# USB_TO_UART.net
KiCad netlist of a schematic drawn in Altium Designer
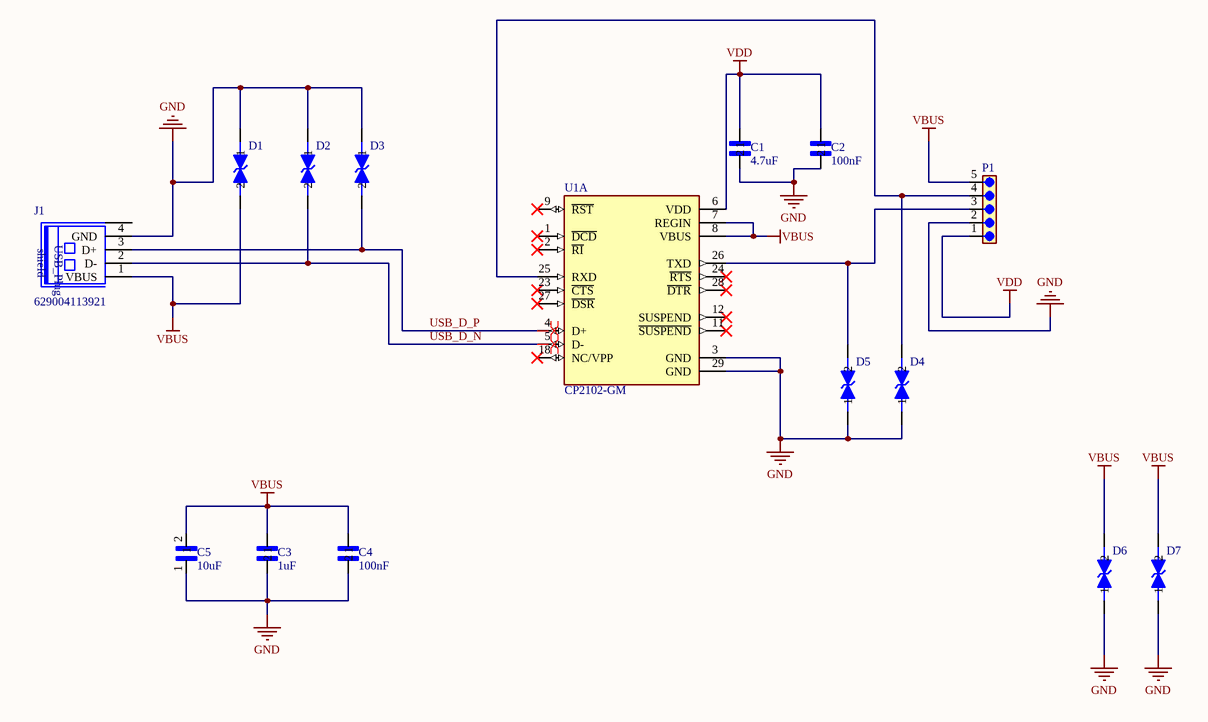
[diagram p0: USB_TO_UART_.SchDoc]

(export (version "E")
  (design (tool "Eeschema 10.0.6"))
  (components
    (comp (ref "C1")
      (value "4.7uF")
      (footprint "CAPC1005X65N")
      (fields (field (name "MF") "TDK") (field (name "MP") "C1005X5R1A475K050BC."))
      (libsource (lib "C1") (part "C1005X5R1A475K050BC"))
    )
    (comp (ref "C2")
      (value "100nF")
      (footprint "CAPC1005X55N")
      (description "0.1 ÂµF Â±10% 16V Ceramic Capacitor X7R 0402 (1005 Metric)")
      (fields (field (name "MF") "Yageo") (field (name "MP") "CC0402KRX7R7BB104"))
      (libsource (lib "C2") (part "CC0402KRX7R7BB104"))
    )
    (comp (ref "C3")
      (value "1uF")
      (footprint "CAPC1005X55N")
      (description "1 ÂµF Â±10% 10V Ceramic Capacitor X5R 0402 (1005 Metric)")
      (fields (field (name "MF") "KEMET") (field (name "MP") "C0402C105K8PACTU"))
      (libsource (lib "C3") (part "C0402C105K8PACTU"))
    )
    (comp (ref "C4")
      (value "100nF")
      (footprint "CAPC1005X55N")
      (description "0.1 ÂµF Â±10% 16V Ceramic Capacitor X7R 0402 (1005 Metric)")
      (fields (field (name "MF") "Yageo") (field (name "MP") "CC0402KRX7R7BB104"))
      (libsource (lib "C4") (part "CC0402KRX7R7BB104"))
    )
    (comp (ref "C5")
      (value "10uF")
      (footprint "CAPC1608X90N")
      (description "10ÂµF Â±10% 10V Ceramic Capacitor X5R 0603 (1608 Metric)")
      (fields (field (name "MP") "C1608X5R1A106K080AC") (field (name "MF") "TDK"))
      (libsource (lib "C5") (part "C1608X5R1A106K080AC"))
    )
    (comp (ref "D1")
      (value "~")
      (footprint "DIO_TPD1E10B06DPYR")
      (description "12-pF, Â±5.5V, Â±30-kV ESD protection diode in 0402 and SOD-523 package")
      (fields (field (name "MF") "Texas Instruments") (field (name "MP") "TPD1E10B06DPYR"))
      (libsource (lib "TPD1E10B06DPYR") (part "TPD1E10B06DPYR"))
    )
    (comp (ref "D2")
      (value "~")
      (footprint "DIO_TPD1E10B06DPYR")
      (description "12-pF, Â±5.5V, Â±30-kV ESD protection diode in 0402 and SOD-523 package")
      (fields (field (name "MF") "Texas Instruments") (field (name "MP") "TPD1E10B06DPYR"))
      (libsource (lib "TPD1E10B06DPYR") (part "TPD1E10B06DPYR"))
    )
    (comp (ref "D3")
      (value "~")
      (footprint "DIO_TPD1E10B06DPYR")
      (description "12-pF, Â±5.5V, Â±30-kV ESD protection diode in 0402 and SOD-523 package")
      (fields (field (name "MF") "Texas Instruments") (field (name "MP") "TPD1E10B06DPYR"))
      (libsource (lib "TPD1E10B06DPYR") (part "TPD1E10B06DPYR"))
    )
    (comp (ref "D4")
      (value "~")
      (footprint "DIO_TPD1E10B06DPYR")
      (description "12-pF, Â±5.5V, Â±30-kV ESD protection diode in 0402 and SOD-523 package")
      (fields (field (name "MF") "Texas Instruments") (field (name "MP") "TPD1E10B06DPYR"))
      (libsource (lib "TPD1E10B06DPYR") (part "TPD1E10B06DPYR"))
    )
    (comp (ref "D5")
      (value "~")
      (footprint "DIO_TPD1E10B06DPYR")
      (description "12-pF, Â±5.5V, Â±30-kV ESD protection diode in 0402 and SOD-523 package")
      (fields (field (name "MF") "Texas Instruments") (field (name "MP") "TPD1E10B06DPYR"))
      (libsource (lib "TPD1E10B06DPYR") (part "TPD1E10B06DPYR"))
    )
    (comp (ref "D6")
      (value "~")
      (footprint "DIO_TPD1E10B06DPYR")
      (description "12-pF, Â±5.5V, Â±30-kV ESD protection diode in 0402 and SOD-523 package")
      (fields (field (name "MF") "Texas Instruments") (field (name "MP") "TPD1E10B06DPYR"))
      (libsource (lib "TPD1E10B06DPYR") (part "TPD1E10B06DPYR"))
    )
    (comp (ref "D7")
      (value "~")
      (footprint "DIO_TPD1E10B06DPYR")
      (description "12-pF, Â±5.5V, Â±30-kV ESD protection diode in 0402 and SOD-523 package")
      (fields (field (name "MF") "Texas Instruments") (field (name "MP") "TPD1E10B06DPYR"))
      (libsource (lib "TPD1E10B06DPYR") (part "TPD1E10B06DPYR"))
    )
    (comp (ref "J1")
      (value "629004113921")
      (footprint "629004113921")
      (description "Type A Plug Horizontal SMT - with Clips")
      (fields (field (name "MF") "Wurth Electronics"))
      (libsource (lib "USB_J1") (part "629004113921"))
    )
    (comp (ref "P1")
      (value "~")
      (footprint "61300511021")
      (description "5 pins, 1 row, right angled, gold plating")
      (fields (field (name "MF") "Wurth Electronics") (field (name "MP") "61300511021"))
      (libsource (lib "6130XX11021_61300511021") (part "6130XX11021_61300511021"))
    )
    (comp (ref "U1A")
      (value "CP2102-GM")
      (footprint "QFN50P500X500X100-29N")
      (description "USB Bridge, USB to UART USB 2.0 UART Interface 28-QFN (5x5)")
      (fields (field (name "MF") "Silicon Labs"))
      (libsource (lib "CP2102-GM") (part "CP2102-GM"))
    )
  )
  (nets
    (net (code "1") (name "/USB_D_N") (class "Default")
      (node (ref "D2") (pin "2") (pinfunction "2_2") (pintype "passive"))
      (node (ref "J1") (pin "2") (pinfunction "D-_2") (pintype "passive"))
      (node (ref "U1A") (pin "5") (pinfunction "D-_5") (pintype "bidirectional"))
    )
    (net (code "2") (name "/USB_D_P") (class "Default")
      (node (ref "D3") (pin "2") (pinfunction "2_2") (pintype "passive"))
      (node (ref "J1") (pin "3") (pinfunction "D+_3") (pintype "passive"))
      (node (ref "U1A") (pin "4") (pinfunction "D+_4") (pintype "bidirectional"))
    )
    (net (code "3") (name "GND") (class "Default")
      (node (ref "C1") (pin "1") (pinfunction "1_1") (pintype "passive"))
      (node (ref "C2") (pin "1") (pinfunction "1_1") (pintype "passive"))
      (node (ref "C3") (pin "1") (pinfunction "1_1") (pintype "passive"))
      (node (ref "C4") (pin "1") (pinfunction "1_1") (pintype "passive"))
      (node (ref "C5") (pin "1") (pinfunction "1_1") (pintype "passive"))
      (node (ref "D1") (pin "1") (pinfunction "1_1") (pintype "passive"))
      (node (ref "D2") (pin "1") (pinfunction "1_1") (pintype "passive"))
      (node (ref "D3") (pin "1") (pinfunction "1_1") (pintype "passive"))
      (node (ref "D4") (pin "1") (pinfunction "1_1") (pintype "passive"))
      (node (ref "D5") (pin "1") (pinfunction "1_1") (pintype "passive"))
      (node (ref "D6") (pin "1") (pinfunction "1_1") (pintype "passive"))
      (node (ref "D7") (pin "1") (pinfunction "1_1") (pintype "passive"))
      (node (ref "J1") (pin "4") (pinfunction "GND_4") (pintype "passive"))
      (node (ref "P1") (pin "2") (pinfunction "2_2") (pintype "passive"))
      (node (ref "U1A") (pin "29") (pinfunction "GND_29") (pintype "power_in"))
      (node (ref "U1A") (pin "3") (pinfunction "GND_3") (pintype "power_in"))
    )
    (net (code "4") (name "Net-(J1-SHIELD-PadS1)") (class "Default")
      (node (ref "J1") (pin "S1") (pinfunction "SHIELD_S1") (pintype "passive"))
      (node (ref "J1") (pin "S2") (pinfunction "SHIELD_S2") (pintype "passive"))
    )
    (net (code "5") (name "Net-(U1A-RXD)") (class "Default")
      (node (ref "D4") (pin "2") (pinfunction "2_2") (pintype "passive"))
      (node (ref "P1") (pin "4") (pinfunction "4_4") (pintype "passive"))
      (node (ref "U1A") (pin "25") (pinfunction "RXD_25") (pintype "input"))
    )
    (net (code "6") (name "Net-(U1A-TXD)") (class "Default")
      (node (ref "D5") (pin "2") (pinfunction "2_2") (pintype "passive"))
      (node (ref "P1") (pin "3") (pinfunction "3_3") (pintype "passive"))
      (node (ref "U1A") (pin "26") (pinfunction "TXD_26") (pintype "output"))
    )
    (net (code "7") (name "VBUS") (class "Default")
      (node (ref "C3") (pin "2") (pinfunction "2_2") (pintype "passive"))
      (node (ref "C4") (pin "2") (pinfunction "2_2") (pintype "passive"))
      (node (ref "C5") (pin "2") (pinfunction "2_2") (pintype "passive"))
      (node (ref "D1") (pin "2") (pinfunction "2_2") (pintype "passive"))
      (node (ref "D6") (pin "2") (pinfunction "2_2") (pintype "passive"))
      (node (ref "D7") (pin "2") (pinfunction "2_2") (pintype "passive"))
      (node (ref "J1") (pin "1") (pinfunction "VBUS_1") (pintype "passive"))
      (node (ref "P1") (pin "5") (pinfunction "5_5") (pintype "passive"))
      (node (ref "U1A") (pin "7") (pinfunction "REGIN_7") (pintype "power_in"))
      (node (ref "U1A") (pin "8") (pinfunction "VBUS_8") (pintype "power_in"))
    )
    (net (code "8") (name "VDD") (class "Default")
      (node (ref "C1") (pin "2") (pinfunction "2_2") (pintype "passive"))
      (node (ref "C2") (pin "2") (pinfunction "2_2") (pintype "passive"))
      (node (ref "P1") (pin "1") (pinfunction "1_1") (pintype "passive"))
      (node (ref "U1A") (pin "6") (pinfunction "VDD_6") (pintype "power_in"))
    )
    (net (code "9") (name "unconnected-(U1A-NC{slash}VPP-Pad18)") (class "Default")
      (node (ref "U1A") (pin "18") (pinfunction "NC/VPP_18") (pintype "bidirectional+no_connect"))
    )
    (net (code "10") (name "unconnected-(U1A-SUSPEND-Pad12)") (class "Default")
      (node (ref "U1A") (pin "12") (pinfunction "SUSPEND_12") (pintype "output+no_connect"))
    )
    (net (code "11") (name "unconnected-(U1A-~{CTS}-Pad23)") (class "Default")
      (node (ref "U1A") (pin "23") (pinfunction "~{CTS}_23") (pintype "input+no_connect"))
    )
    (net (code "12") (name "unconnected-(U1A-~{DCD}-Pad1)") (class "Default")
      (node (ref "U1A") (pin "1") (pinfunction "~{DCD}_1") (pintype "input+no_connect"))
    )
    (net (code "13") (name "unconnected-(U1A-~{DSR}-Pad27)") (class "Default")
      (node (ref "U1A") (pin "27") (pinfunction "~{DSR}_27") (pintype "input+no_connect"))
    )
    (net (code "14") (name "unconnected-(U1A-~{DTR}-Pad28)") (class "Default")
      (node (ref "U1A") (pin "28") (pinfunction "~{DTR}_28") (pintype "output+no_connect"))
    )
    (net (code "15") (name "unconnected-(U1A-~{RI}-Pad2)") (class "Default")
      (node (ref "U1A") (pin "2") (pinfunction "~{RI}_2") (pintype "input+no_connect"))
    )
    (net (code "16") (name "unconnected-(U1A-~{RST}-Pad9)") (class "Default")
      (node (ref "U1A") (pin "9") (pinfunction "~{RST}_9") (pintype "bidirectional+no_connect"))
    )
    (net (code "17") (name "unconnected-(U1A-~{RTS}-Pad24)") (class "Default")
      (node (ref "U1A") (pin "24") (pinfunction "~{RTS}_24") (pintype "output+no_connect"))
    )
    (net (code "18") (name "unconnected-(U1A-~{SUSPEND}-Pad11)") (class "Default")
      (node (ref "U1A") (pin "11") (pinfunction "~{SUSPEND}_11") (pintype "output+no_connect"))
    )
  )
)
